# CAN.net
KiCad netlist of a schematic drawn in Altium Designer
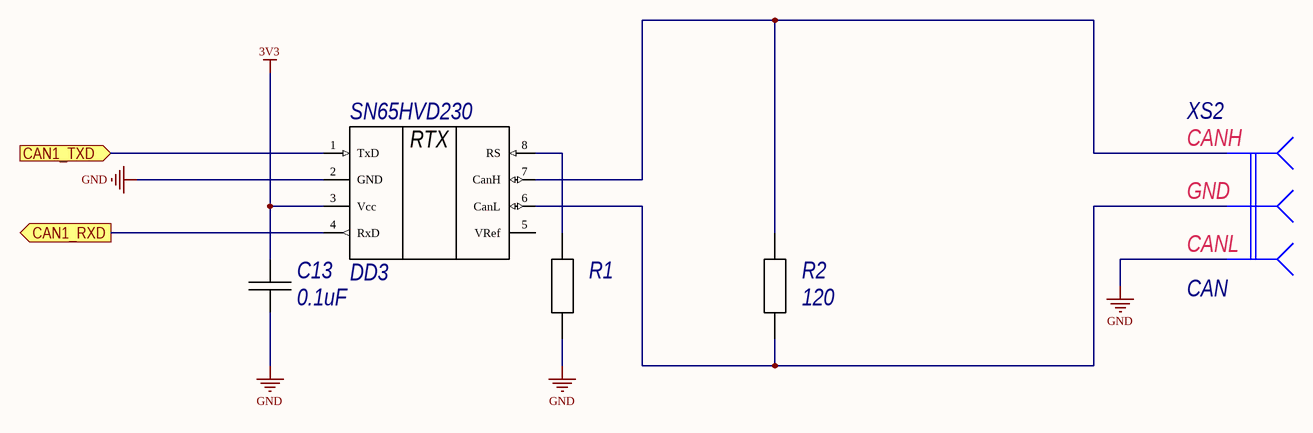
[diagram p0: CAN.SchDoc]

(export (version "E")
  (design (tool "Eeschema 10.0.6"))
  (components
    (comp (ref "C13")
      (value "0.1uF")
      (footprint "C0805C")
      (fields (field (name "PUBLISHER") "Andrew Danich"))
      (libsource (lib "PA_control_board") (part "CAP_0805"))
    )
    (comp (ref "DD3")
      (value "SN65HVD230")
      (footprint "SOIC8 (SO-8)")
      (description "Высокоскоростной CAN-Трансивер, 1Мб/с, 12В/24В, до 112 узлов")
      (fields (field (name "PUBLISHER") "Andrew Danich"))
      (libsource (lib "PA_control_board") (part "SN65HVD230"))
    )
    (comp (ref "R1")
      (value "R0805")
      (footprint "C0805R")
      (fields (field (name "PUBLISHER") "Andrew Danich"))
      (libsource (lib "PA_control_board") (part "R0805"))
    )
    (comp (ref "R2")
      (value "120")
      (footprint "C0805R")
      (fields (field (name "PUBLISHER") "Andrew Danich"))
      (libsource (lib "PA_control_board") (part "R0805"))
    )
    (comp (ref "XS2")
      (value "CAN")
      (footprint "YX-XH-3")
      (fields (field (name "PUBLISHER") "Andrew Danich"))
      (libsource (lib "PA_control_board") (part "CONNECT_CAN"))
    )
  )
  (nets
    (net (code "1") (name "/CAN1_RXD") (class "Default")
      (node (ref "DD3") (pin "4") (pinfunction "RxD_4") (pintype "output"))
    )
    (net (code "2") (name "/CAN1_TXD") (class "Default")
      (node (ref "DD3") (pin "1") (pinfunction "TxD_1") (pintype "input"))
    )
    (net (code "3") (name "3V3") (class "Default")
      (node (ref "C13") (pin "2") (pinfunction "2_2") (pintype "passive"))
      (node (ref "DD3") (pin "3") (pinfunction "Vcc_3") (pintype "power_in"))
    )
    (net (code "4") (name "GND") (class "Default")
      (node (ref "C13") (pin "1") (pinfunction "1_1") (pintype "passive"))
      (node (ref "DD3") (pin "2") (pinfunction "GND_2") (pintype "power_in"))
      (node (ref "R1") (pin "2") (pinfunction "2_2") (pintype "passive"))
      (node (ref "XS2") (pin "3") (pintype "passive"))
    )
    (net (code "5") (name "Net-(DD3-CanH)") (class "Default")
      (node (ref "DD3") (pin "7") (pinfunction "CanH_7") (pintype "bidirectional"))
      (node (ref "R2") (pin "1") (pinfunction "1_1") (pintype "passive"))
      (node (ref "XS2") (pin "1") (pintype "passive"))
    )
    (net (code "6") (name "Net-(DD3-CanL)") (class "Default")
      (node (ref "DD3") (pin "6") (pinfunction "CanL_6") (pintype "bidirectional"))
      (node (ref "R2") (pin "2") (pinfunction "2_2") (pintype "passive"))
      (node (ref "XS2") (pin "2") (pintype "passive"))
    )
    (net (code "7") (name "Net-(DD3-RS)") (class "Default")
      (node (ref "DD3") (pin "8") (pinfunction "RS_8") (pintype "input"))
      (node (ref "R1") (pin "1") (pinfunction "1_1") (pintype "passive"))
    )
    (net (code "8") (name "unconnected-(DD3-VRef-Pad5)") (class "Default")
      (node (ref "DD3") (pin "5") (pinfunction "VRef_5") (pintype "power_in"))
    )
  )
)
